# 8steps.net
KiCad netlist of a schematic drawn in EAGLE
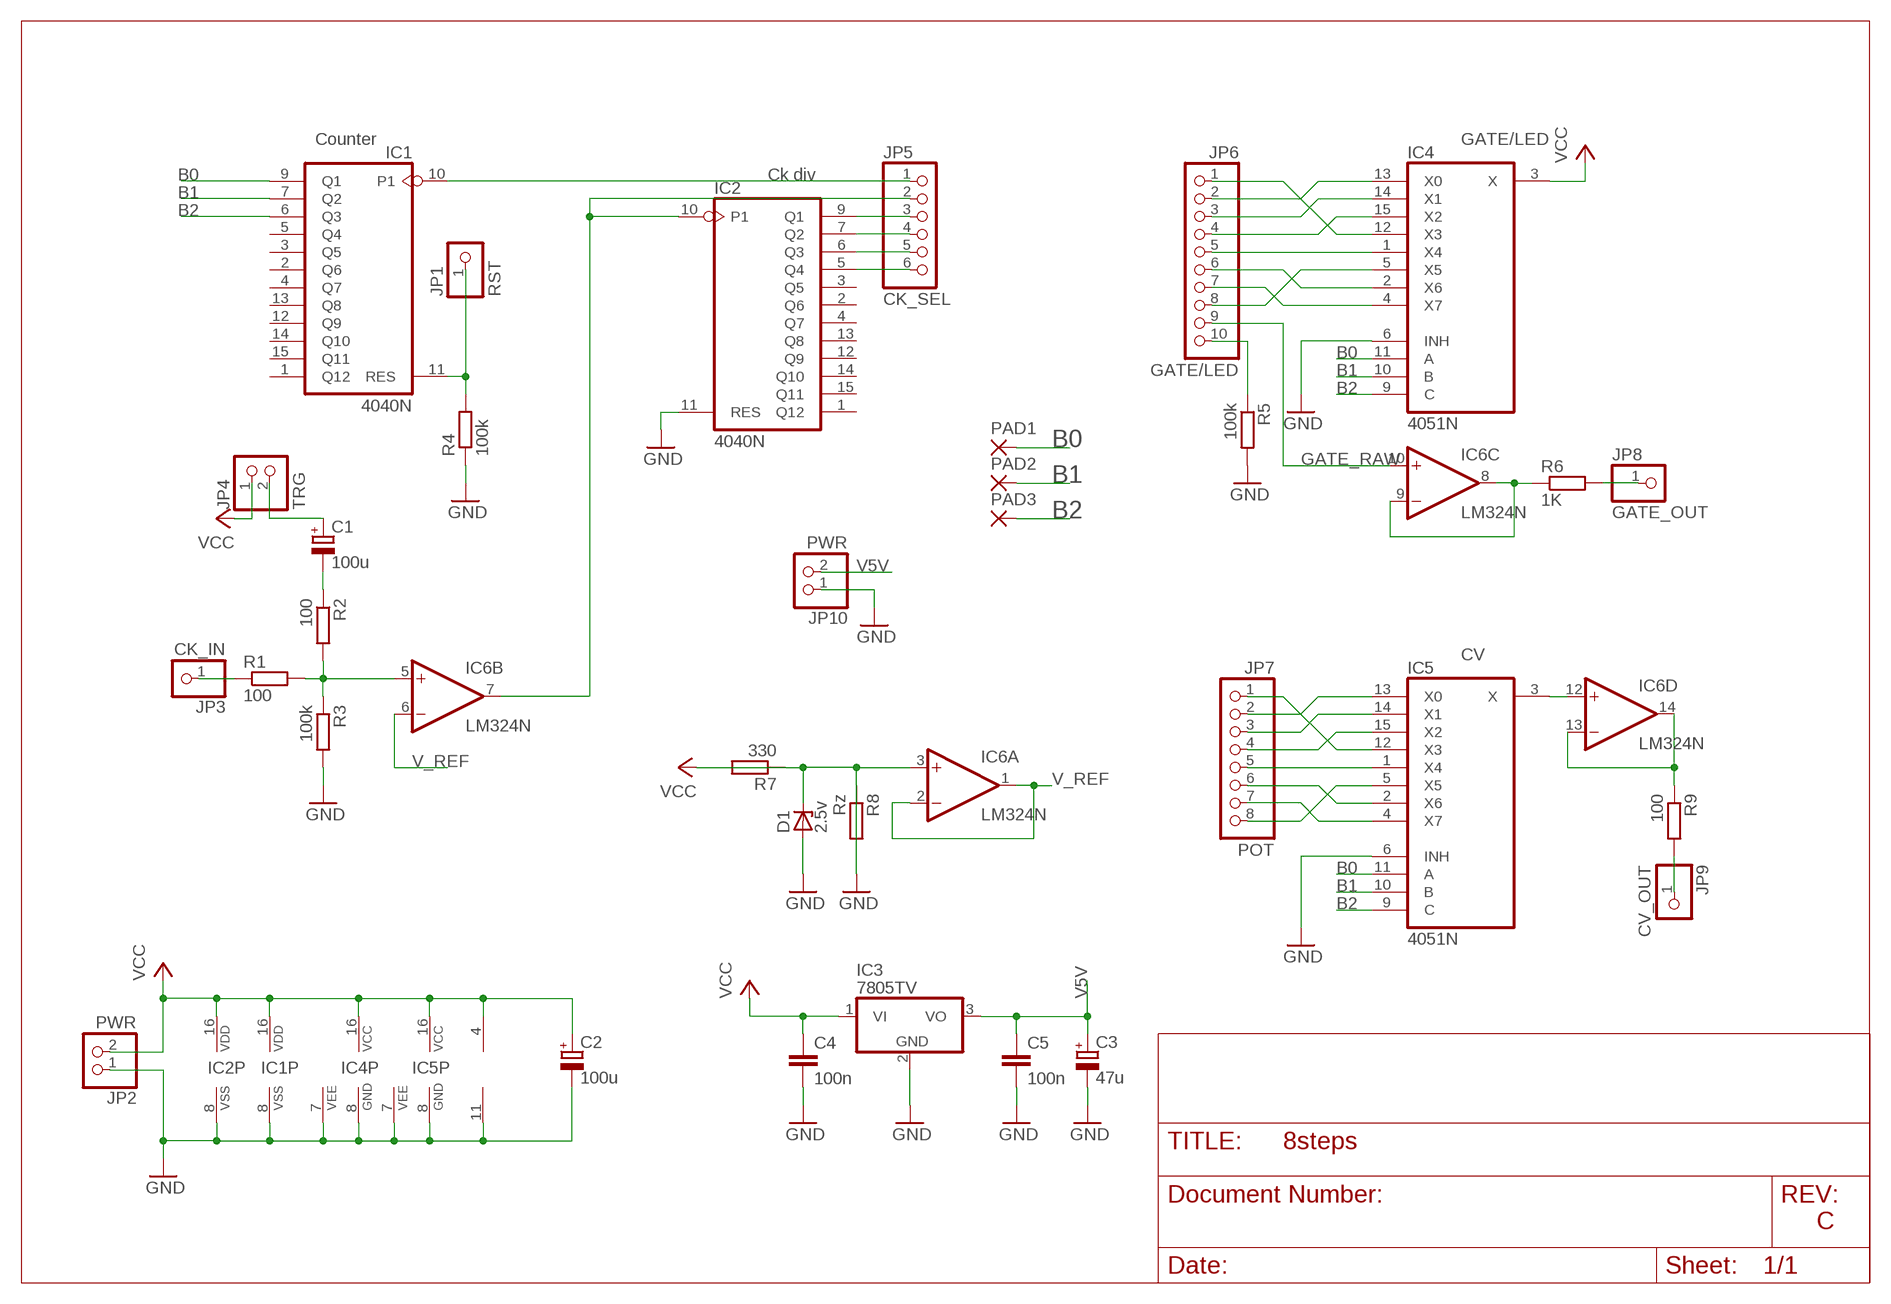
[diagram p0: schematic, sheet 1]

(export (version "E")
  (design (tool "Eeschema 10.0.6"))
  (components
    (comp (ref "C1")
      (value "100u")
      (footprint "eagle-import:E2,5-7")
      (libsource (lib "eagle-import") (part "CPOL-EUE2.5-7"))
    )
    (comp (ref "C2")
      (value "100u")
      (footprint "eagle-import:E2,5-7")
      (libsource (lib "eagle-import") (part "CPOL-EUE2.5-7"))
    )
    (comp (ref "C3")
      (value "47u")
      (footprint "eagle-import:E2,5-7")
      (libsource (lib "eagle-import") (part "CPOL-EUE2.5-7"))
    )
    (comp (ref "C4")
      (value "100n")
      (footprint "eagle-import:C050-025X075")
      (libsource (lib "eagle-import") (part "C-EU050-025X075"))
    )
    (comp (ref "C5")
      (value "100n")
      (footprint "eagle-import:C050-025X075")
      (libsource (lib "eagle-import") (part "C-EU050-025X075"))
    )
    (comp (ref "D1")
      (value "2.5v")
      (footprint "eagle-import:ZDIO-2.5")
      (libsource (lib "eagle-import") (part "ZENER-DIODEZD-2.5"))
    )
    (comp (ref "IC1")
      (value "4040N")
      (footprint "eagle-import:DIL16")
      (libsource (lib "eagle-import") (part "4040N"))
    )
    (comp (ref "IC2")
      (value "4040N")
      (footprint "eagle-import:DIL16")
      (libsource (lib "eagle-import") (part "4040N"))
    )
    (comp (ref "IC3")
      (value "7805TV")
      (footprint "eagle-import:TO220V")
      (libsource (lib "eagle-import") (part "78TV05"))
    )
    (comp (ref "IC4")
      (value "4051N")
      (footprint "eagle-import:DIL16")
      (libsource (lib "eagle-import") (part "4051N"))
    )
    (comp (ref "IC5")
      (value "4051N")
      (footprint "eagle-import:DIL16")
      (libsource (lib "eagle-import") (part "4051N"))
    )
    (comp (ref "IC6")
      (value "LM324N")
      (footprint "eagle-import:DIL14")
      (libsource (lib "eagle-import") (part "LM324N"))
    )
    (comp (ref "JP1")
      (value "RST")
      (footprint "eagle-import:1X01")
      (libsource (lib "eagle-import") (part "PINHD-1X1"))
    )
    (comp (ref "JP2")
      (value "PWR")
      (footprint "eagle-import:1X02")
      (libsource (lib "eagle-import") (part "PINHD-1X2"))
    )
    (comp (ref "JP3")
      (value "CK_IN")
      (footprint "eagle-import:1X01")
      (libsource (lib "eagle-import") (part "PINHD-1X1"))
    )
    (comp (ref "JP4")
      (value "TRG")
      (footprint "eagle-import:1X02")
      (libsource (lib "eagle-import") (part "PINHD-1X2"))
    )
    (comp (ref "JP5")
      (value "CK_SEL")
      (footprint "eagle-import:1X06")
      (libsource (lib "eagle-import") (part "PINHD-1X6"))
    )
    (comp (ref "JP6")
      (value "GATE/LED")
      (footprint "eagle-import:1X10")
      (libsource (lib "eagle-import") (part "PINHD-1X10"))
    )
    (comp (ref "JP7")
      (value "POT")
      (footprint "eagle-import:1X08")
      (libsource (lib "eagle-import") (part "PINHD-1X8"))
    )
    (comp (ref "JP8")
      (value "GATE_OUT")
      (footprint "eagle-import:1X01")
      (libsource (lib "eagle-import") (part "PINHD-1X1"))
    )
    (comp (ref "JP9")
      (value "CV_OUT")
      (footprint "eagle-import:1X01")
      (libsource (lib "eagle-import") (part "PINHD-1X1"))
    )
    (comp (ref "JP10")
      (value "PWR")
      (footprint "eagle-import:1X02")
      (libsource (lib "eagle-import") (part "PINHD-1X2"))
    )
    (comp (ref "PAD1")
      (value "WIREPADSMD1,27-254")
      (footprint "eagle-import:SMD1,27-2,54")
      (libsource (lib "eagle-import") (part "WIREPADSMD1,27-254"))
    )
    (comp (ref "PAD2")
      (value "WIREPADSMD1,27-254")
      (footprint "eagle-import:SMD1,27-2,54")
      (libsource (lib "eagle-import") (part "WIREPADSMD1,27-254"))
    )
    (comp (ref "PAD3")
      (value "WIREPADSMD1,27-254")
      (footprint "eagle-import:SMD1,27-2,54")
      (libsource (lib "eagle-import") (part "WIREPADSMD1,27-254"))
    )
    (comp (ref "R1")
      (value "100")
      (footprint "eagle-import:0207_2V")
      (libsource (lib "eagle-import") (part "R-EU_0207/2V"))
    )
    (comp (ref "R2")
      (value "100")
      (footprint "eagle-import:0207_2V")
      (libsource (lib "eagle-import") (part "R-EU_0207/2V"))
    )
    (comp (ref "R3")
      (value "100k")
      (footprint "eagle-import:0204_7")
      (libsource (lib "eagle-import") (part "R-EU_0204/7"))
    )
    (comp (ref "R4")
      (value "100k")
      (footprint "eagle-import:0207_2V")
      (libsource (lib "eagle-import") (part "R-EU_0207/2V"))
    )
    (comp (ref "R5")
      (value "100k")
      (footprint "eagle-import:0207_2V")
      (libsource (lib "eagle-import") (part "R-EU_0207/2V"))
    )
    (comp (ref "R6")
      (value "1K")
      (footprint "eagle-import:0207_2V")
      (libsource (lib "eagle-import") (part "R-EU_0207/2V"))
    )
    (comp (ref "R7")
      (value "330")
      (footprint "eagle-import:0207_2V")
      (libsource (lib "eagle-import") (part "R-EU_0207/2V"))
    )
    (comp (ref "R8")
      (value "Rz")
      (footprint "eagle-import:0207_2V")
      (libsource (lib "eagle-import") (part "R-EU_0207/2V"))
    )
    (comp (ref "R9")
      (value "100")
      (footprint "eagle-import:0207_2V")
      (libsource (lib "eagle-import") (part "R-EU_0207/2V"))
    )
  )
  (nets
    (net (code "1") (name "/B0") (class "Default")
      (node (ref "IC1") (pin "9") (pinfunction "Q1_9") (pintype "output"))
      (node (ref "IC4") (pin "11") (pinfunction "A_11") (pintype "input"))
      (node (ref "IC5") (pin "11") (pinfunction "A_11") (pintype "input"))
      (node (ref "PAD1") (pin "1") (pinfunction "P_1") (pintype "passive"))
    )
    (net (code "2") (name "/B1") (class "Default")
      (node (ref "IC1") (pin "7") (pinfunction "Q2_7") (pintype "output"))
      (node (ref "IC4") (pin "10") (pinfunction "B_10") (pintype "input"))
      (node (ref "IC5") (pin "10") (pinfunction "B_10") (pintype "input"))
      (node (ref "PAD2") (pin "1") (pinfunction "P_1") (pintype "passive"))
    )
    (net (code "3") (name "/B2") (class "Default")
      (node (ref "IC1") (pin "6") (pinfunction "Q3_6") (pintype "output"))
      (node (ref "IC4") (pin "9") (pinfunction "C_9") (pintype "input"))
      (node (ref "IC5") (pin "9") (pinfunction "C_9") (pintype "input"))
      (node (ref "PAD3") (pin "1") (pinfunction "P_1") (pintype "passive"))
    )
    (net (code "4") (name "/GATE_RAW") (class "Default")
      (node (ref "IC6") (pin "10") (pinfunction "+IN_10") (pintype "input"))
      (node (ref "JP6") (pin "9") (pinfunction "9_9") (pintype "passive"))
    )
    (net (code "5") (name "/V5V") (class "Default")
      (node (ref "C3") (pin "+") (pinfunction "+_+") (pintype "passive"))
      (node (ref "C5") (pin "1") (pinfunction "1_1") (pintype "passive"))
      (node (ref "IC3") (pin "3") (pinfunction "VO_3") (pintype "passive"))
      (node (ref "JP10") (pin "2") (pinfunction "2_2") (pintype "passive"))
    )
    (net (code "6") (name "/V_REF") (class "Default")
      (node (ref "IC6") (pin "1") (pinfunction "OUT_1") (pintype "output"))
      (node (ref "IC6") (pin "2") (pinfunction "-IN_2") (pintype "input"))
      (node (ref "IC6") (pin "6") (pinfunction "-IN_6") (pintype "input"))
    )
    (net (code "7") (name "GND") (class "Default")
      (node (ref "C2") (pin "-") (pinfunction "-_-") (pintype "passive"))
      (node (ref "C3") (pin "-") (pinfunction "-_-") (pintype "passive"))
      (node (ref "C4") (pin "2") (pinfunction "2_2") (pintype "passive"))
      (node (ref "C5") (pin "2") (pinfunction "2_2") (pintype "passive"))
      (node (ref "D1") (pin "A") (pinfunction "A_A") (pintype "passive"))
      (node (ref "IC1") (pin "8") (pinfunction "VSS_8") (pintype "power_in"))
      (node (ref "IC2") (pin "11") (pinfunction "RES_11") (pintype "input"))
      (node (ref "IC2") (pin "8") (pinfunction "VSS_8") (pintype "power_in"))
      (node (ref "IC3") (pin "2") (pinfunction "GND_2") (pintype "passive"))
      (node (ref "IC4") (pin "6") (pinfunction "INH_6") (pintype "input"))
      (node (ref "IC4") (pin "7") (pinfunction "VEE_7") (pintype "power_in"))
      (node (ref "IC4") (pin "8") (pinfunction "GND_8") (pintype "power_in"))
      (node (ref "IC5") (pin "6") (pinfunction "INH_6") (pintype "input"))
      (node (ref "IC5") (pin "7") (pinfunction "VEE_7") (pintype "power_in"))
      (node (ref "IC5") (pin "8") (pinfunction "GND_8") (pintype "power_in"))
      (node (ref "IC6") (pin "11") (pinfunction "V-_11") (pintype "power_in"))
      (node (ref "JP10") (pin "1") (pinfunction "1_1") (pintype "passive"))
      (node (ref "JP2") (pin "1") (pinfunction "1_1") (pintype "passive"))
      (node (ref "R3") (pin "2") (pinfunction "2_2") (pintype "passive"))
      (node (ref "R4") (pin "1") (pinfunction "1_1") (pintype "passive"))
      (node (ref "R5") (pin "2") (pinfunction "2_2") (pintype "passive"))
      (node (ref "R8") (pin "1") (pinfunction "1_1") (pintype "passive"))
    )
    (net (code "8") (name "Net-(C1-Pad+)") (class "Default")
      (node (ref "C1") (pin "+") (pinfunction "+_+") (pintype "passive"))
      (node (ref "JP4") (pin "2") (pinfunction "2_2") (pintype "passive"))
    )
    (net (code "9") (name "Net-(C1-Pad-)") (class "Default")
      (node (ref "C1") (pin "-") (pinfunction "-_-") (pintype "passive"))
      (node (ref "R2") (pin "1") (pinfunction "1_1") (pintype "passive"))
    )
    (net (code "10") (name "Net-(IC1A-P1)") (class "Default")
      (node (ref "IC1") (pin "10") (pinfunction "P1_10") (pintype "input"))
      (node (ref "JP5") (pin "1") (pinfunction "1_1") (pintype "passive"))
    )
    (net (code "11") (name "Net-(IC1A-RES)") (class "Default")
      (node (ref "IC1") (pin "11") (pinfunction "RES_11") (pintype "input"))
      (node (ref "JP1") (pin "1") (pinfunction "1_1") (pintype "passive"))
      (node (ref "R4") (pin "2") (pinfunction "2_2") (pintype "passive"))
    )
    (net (code "12") (name "Net-(IC2A-P1)") (class "Default")
      (node (ref "IC2") (pin "10") (pinfunction "P1_10") (pintype "input"))
      (node (ref "IC6") (pin "7") (pinfunction "OUT_7") (pintype "output"))
      (node (ref "JP5") (pin "2") (pinfunction "2_2") (pintype "passive"))
    )
    (net (code "13") (name "Net-(IC2A-Q1)") (class "Default")
      (node (ref "IC2") (pin "9") (pinfunction "Q1_9") (pintype "output"))
      (node (ref "JP5") (pin "3") (pinfunction "3_3") (pintype "passive"))
    )
    (net (code "14") (name "Net-(IC2A-Q2)") (class "Default")
      (node (ref "IC2") (pin "7") (pinfunction "Q2_7") (pintype "output"))
      (node (ref "JP5") (pin "4") (pinfunction "4_4") (pintype "passive"))
    )
    (net (code "15") (name "Net-(IC2A-Q3)") (class "Default")
      (node (ref "IC2") (pin "6") (pinfunction "Q3_6") (pintype "output"))
      (node (ref "JP5") (pin "5") (pinfunction "5_5") (pintype "passive"))
    )
    (net (code "16") (name "Net-(IC2A-Q4)") (class "Default")
      (node (ref "IC2") (pin "5") (pinfunction "Q4_5") (pintype "output"))
      (node (ref "JP5") (pin "6") (pinfunction "6_6") (pintype "passive"))
    )
    (net (code "17") (name "Net-(IC4A-X0)") (class "Default")
      (node (ref "IC4") (pin "13") (pinfunction "X0_13") (pintype "bidirectional"))
      (node (ref "JP6") (pin "2") (pinfunction "2_2") (pintype "passive"))
    )
    (net (code "18") (name "Net-(IC4A-X1)") (class "Default")
      (node (ref "IC4") (pin "14") (pinfunction "X1_14") (pintype "bidirectional"))
      (node (ref "JP6") (pin "3") (pinfunction "3_3") (pintype "passive"))
    )
    (net (code "19") (name "Net-(IC4A-X2)") (class "Default")
      (node (ref "IC4") (pin "15") (pinfunction "X2_15") (pintype "bidirectional"))
      (node (ref "JP6") (pin "4") (pinfunction "4_4") (pintype "passive"))
    )
    (net (code "20") (name "Net-(IC4A-X3)") (class "Default")
      (node (ref "IC4") (pin "12") (pinfunction "X3_12") (pintype "bidirectional"))
      (node (ref "JP6") (pin "1") (pinfunction "1_1") (pintype "passive"))
    )
    (net (code "21") (name "Net-(IC4A-X4)") (class "Default")
      (node (ref "IC4") (pin "1") (pinfunction "X4_1") (pintype "bidirectional"))
      (node (ref "JP6") (pin "5") (pinfunction "5_5") (pintype "passive"))
    )
    (net (code "22") (name "Net-(IC4A-X5)") (class "Default")
      (node (ref "IC4") (pin "5") (pinfunction "X5_5") (pintype "bidirectional"))
      (node (ref "JP6") (pin "8") (pinfunction "8_8") (pintype "passive"))
    )
    (net (code "23") (name "Net-(IC4A-X6)") (class "Default")
      (node (ref "IC4") (pin "2") (pinfunction "X6_2") (pintype "bidirectional"))
      (node (ref "JP6") (pin "6") (pinfunction "6_6") (pintype "passive"))
    )
    (net (code "24") (name "Net-(IC4A-X7)") (class "Default")
      (node (ref "IC4") (pin "4") (pinfunction "X7_4") (pintype "bidirectional"))
      (node (ref "JP6") (pin "7") (pinfunction "7_7") (pintype "passive"))
    )
    (net (code "25") (name "Net-(IC5A-X)") (class "Default")
      (node (ref "IC5") (pin "3") (pinfunction "X_3") (pintype "bidirectional"))
      (node (ref "IC6") (pin "12") (pinfunction "+IN_12") (pintype "input"))
    )
    (net (code "26") (name "Net-(IC5A-X0)") (class "Default")
      (node (ref "IC5") (pin "13") (pinfunction "X0_13") (pintype "bidirectional"))
      (node (ref "JP7") (pin "2") (pinfunction "2_2") (pintype "passive"))
    )
    (net (code "27") (name "Net-(IC5A-X1)") (class "Default")
      (node (ref "IC5") (pin "14") (pinfunction "X1_14") (pintype "bidirectional"))
      (node (ref "JP7") (pin "3") (pinfunction "3_3") (pintype "passive"))
    )
    (net (code "28") (name "Net-(IC5A-X2)") (class "Default")
      (node (ref "IC5") (pin "15") (pinfunction "X2_15") (pintype "bidirectional"))
      (node (ref "JP7") (pin "4") (pinfunction "4_4") (pintype "passive"))
    )
    (net (code "29") (name "Net-(IC5A-X3)") (class "Default")
      (node (ref "IC5") (pin "12") (pinfunction "X3_12") (pintype "bidirectional"))
      (node (ref "JP7") (pin "1") (pinfunction "1_1") (pintype "passive"))
    )
    (net (code "30") (name "Net-(IC5A-X4)") (class "Default")
      (node (ref "IC5") (pin "1") (pinfunction "X4_1") (pintype "bidirectional"))
      (node (ref "JP7") (pin "5") (pinfunction "5_5") (pintype "passive"))
    )
    (net (code "31") (name "Net-(IC5A-X5)") (class "Default")
      (node (ref "IC5") (pin "5") (pinfunction "X5_5") (pintype "bidirectional"))
      (node (ref "JP7") (pin "8") (pinfunction "8_8") (pintype "passive"))
    )
    (net (code "32") (name "Net-(IC5A-X6)") (class "Default")
      (node (ref "IC5") (pin "2") (pinfunction "X6_2") (pintype "bidirectional"))
      (node (ref "JP7") (pin "6") (pinfunction "6_6") (pintype "passive"))
    )
    (net (code "33") (name "Net-(IC5A-X7)") (class "Default")
      (node (ref "IC5") (pin "4") (pinfunction "X7_4") (pintype "bidirectional"))
      (node (ref "JP7") (pin "7") (pinfunction "7_7") (pintype "passive"))
    )
    (net (code "34") (name "Net-(IC6A-+IN)") (class "Default")
      (node (ref "D1") (pin "C") (pinfunction "C_C") (pintype "passive"))
      (node (ref "IC6") (pin "3") (pinfunction "+IN_3") (pintype "input"))
      (node (ref "R7") (pin "2") (pinfunction "2_2") (pintype "passive"))
      (node (ref "R8") (pin "2") (pinfunction "2_2") (pintype "passive"))
    )
    (net (code "35") (name "Net-(IC6B-+IN)") (class "Default")
      (node (ref "IC6") (pin "5") (pinfunction "+IN_5") (pintype "input"))
      (node (ref "R1") (pin "2") (pinfunction "2_2") (pintype "passive"))
      (node (ref "R2") (pin "2") (pinfunction "2_2") (pintype "passive"))
      (node (ref "R3") (pin "1") (pinfunction "1_1") (pintype "passive"))
    )
    (net (code "36") (name "Net-(IC6C--IN)") (class "Default")
      (node (ref "IC6") (pin "8") (pinfunction "OUT_8") (pintype "output"))
      (node (ref "IC6") (pin "9") (pinfunction "-IN_9") (pintype "input"))
      (node (ref "R6") (pin "1") (pinfunction "1_1") (pintype "passive"))
    )
    (net (code "37") (name "Net-(IC6D--IN)") (class "Default")
      (node (ref "IC6") (pin "13") (pinfunction "-IN_13") (pintype "input"))
      (node (ref "IC6") (pin "14") (pinfunction "OUT_14") (pintype "output"))
      (node (ref "R9") (pin "1") (pinfunction "1_1") (pintype "passive"))
    )
    (net (code "38") (name "Net-(JP3-Pad1)") (class "Default")
      (node (ref "JP3") (pin "1") (pinfunction "1_1") (pintype "passive"))
      (node (ref "R1") (pin "1") (pinfunction "1_1") (pintype "passive"))
    )
    (net (code "39") (name "Net-(JP6-Pad10)") (class "Default")
      (node (ref "JP6") (pin "10") (pinfunction "10_10") (pintype "passive"))
      (node (ref "R5") (pin "1") (pinfunction "1_1") (pintype "passive"))
    )
    (net (code "40") (name "Net-(JP8-Pad1)") (class "Default")
      (node (ref "JP8") (pin "1") (pinfunction "1_1") (pintype "passive"))
      (node (ref "R6") (pin "2") (pinfunction "2_2") (pintype "passive"))
    )
    (net (code "41") (name "Net-(JP9-Pad1)") (class "Default")
      (node (ref "JP9") (pin "1") (pinfunction "1_1") (pintype "passive"))
      (node (ref "R9") (pin "2") (pinfunction "2_2") (pintype "passive"))
    )
    (net (code "42") (name "VCC") (class "Default")
      (node (ref "C2") (pin "+") (pinfunction "+_+") (pintype "passive"))
      (node (ref "C4") (pin "1") (pinfunction "1_1") (pintype "passive"))
      (node (ref "IC1") (pin "16") (pinfunction "VDD_16") (pintype "power_in"))
      (node (ref "IC2") (pin "16") (pinfunction "VDD_16") (pintype "power_in"))
      (node (ref "IC3") (pin "1") (pinfunction "VI_1") (pintype "input"))
      (node (ref "IC4") (pin "16") (pinfunction "VCC_16") (pintype "power_in"))
      (node (ref "IC4") (pin "3") (pinfunction "X_3") (pintype "bidirectional"))
      (node (ref "IC5") (pin "16") (pinfunction "VCC_16") (pintype "power_in"))
      (node (ref "IC6") (pin "4") (pinfunction "V+_4") (pintype "power_in"))
      (node (ref "JP2") (pin "2") (pinfunction "2_2") (pintype "passive"))
      (node (ref "JP4") (pin "1") (pinfunction "1_1") (pintype "passive"))
      (node (ref "R7") (pin "1") (pinfunction "1_1") (pintype "passive"))
    )
    (net (code "43") (name "unconnected-(IC1A-Q4-Pad5)") (class "Default")
      (node (ref "IC1") (pin "5") (pinfunction "Q4_5") (pintype "output"))
    )
    (net (code "44") (name "unconnected-(IC1A-Q5-Pad3)") (class "Default")
      (node (ref "IC1") (pin "3") (pinfunction "Q5_3") (pintype "output"))
    )
    (net (code "45") (name "unconnected-(IC1A-Q6-Pad2)") (class "Default")
      (node (ref "IC1") (pin "2") (pinfunction "Q6_2") (pintype "output"))
    )
    (net (code "46") (name "unconnected-(IC1A-Q7-Pad4)") (class "Default")
      (node (ref "IC1") (pin "4") (pinfunction "Q7_4") (pintype "output"))
    )
    (net (code "47") (name "unconnected-(IC1A-Q8-Pad13)") (class "Default")
      (node (ref "IC1") (pin "13") (pinfunction "Q8_13") (pintype "output"))
    )
    (net (code "48") (name "unconnected-(IC1A-Q9-Pad12)") (class "Default")
      (node (ref "IC1") (pin "12") (pinfunction "Q9_12") (pintype "output"))
    )
    (net (code "49") (name "unconnected-(IC1A-Q10-Pad14)") (class "Default")
      (node (ref "IC1") (pin "14") (pinfunction "Q10_14") (pintype "output"))
    )
    (net (code "50") (name "unconnected-(IC1A-Q11-Pad15)") (class "Default")
      (node (ref "IC1") (pin "15") (pinfunction "Q11_15") (pintype "output"))
    )
    (net (code "51") (name "unconnected-(IC1A-Q12-Pad1)") (class "Default")
      (node (ref "IC1") (pin "1") (pinfunction "Q12_1") (pintype "output"))
    )
    (net (code "52") (name "unconnected-(IC2A-Q5-Pad3)") (class "Default")
      (node (ref "IC2") (pin "3") (pinfunction "Q5_3") (pintype "output"))
    )
    (net (code "53") (name "unconnected-(IC2A-Q6-Pad2)") (class "Default")
      (node (ref "IC2") (pin "2") (pinfunction "Q6_2") (pintype "output"))
    )
    (net (code "54") (name "unconnected-(IC2A-Q7-Pad4)") (class "Default")
      (node (ref "IC2") (pin "4") (pinfunction "Q7_4") (pintype "output"))
    )
    (net (code "55") (name "unconnected-(IC2A-Q8-Pad13)") (class "Default")
      (node (ref "IC2") (pin "13") (pinfunction "Q8_13") (pintype "output"))
    )
    (net (code "56") (name "unconnected-(IC2A-Q9-Pad12)") (class "Default")
      (node (ref "IC2") (pin "12") (pinfunction "Q9_12") (pintype "output"))
    )
    (net (code "57") (name "unconnected-(IC2A-Q10-Pad14)") (class "Default")
      (node (ref "IC2") (pin "14") (pinfunction "Q10_14") (pintype "output"))
    )
    (net (code "58") (name "unconnected-(IC2A-Q11-Pad15)") (class "Default")
      (node (ref "IC2") (pin "15") (pinfunction "Q11_15") (pintype "output"))
    )
    (net (code "59") (name "unconnected-(IC2A-Q12-Pad1)") (class "Default")
      (node (ref "IC2") (pin "1") (pinfunction "Q12_1") (pintype "output"))
    )
  )
)
